# M7.net
KiCad netlist of a schematic drawn in Altium Designer
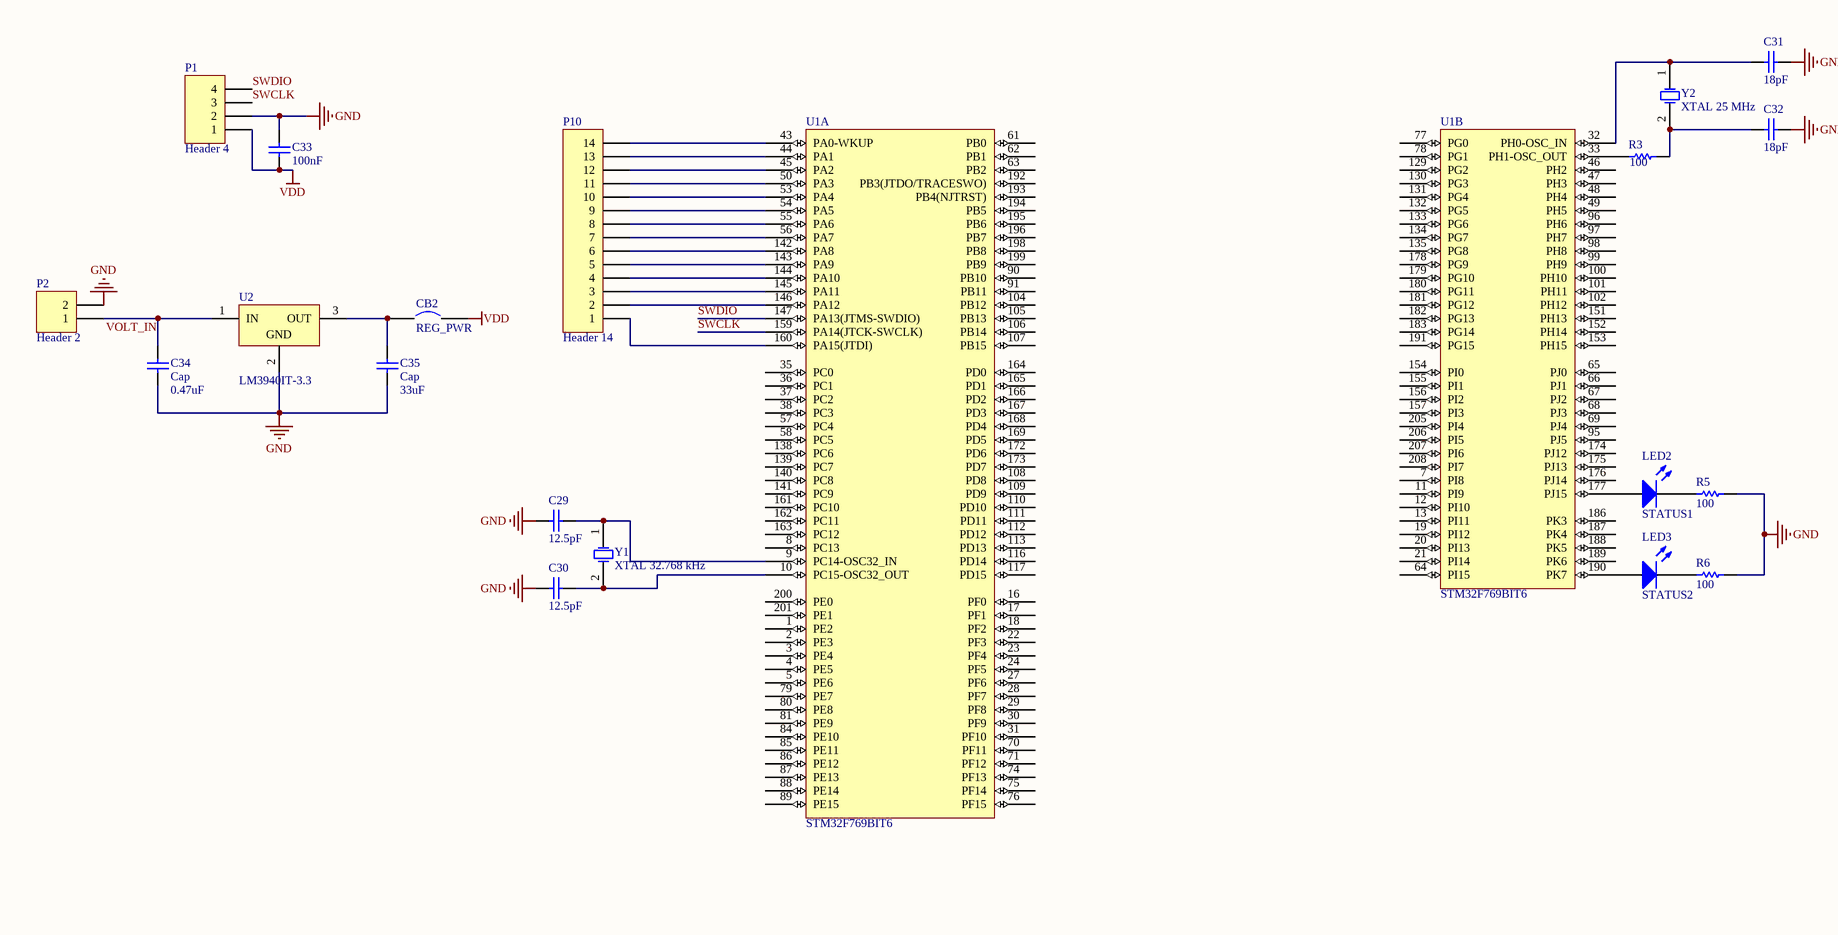
[diagram p0: M7.SchDoc, left]
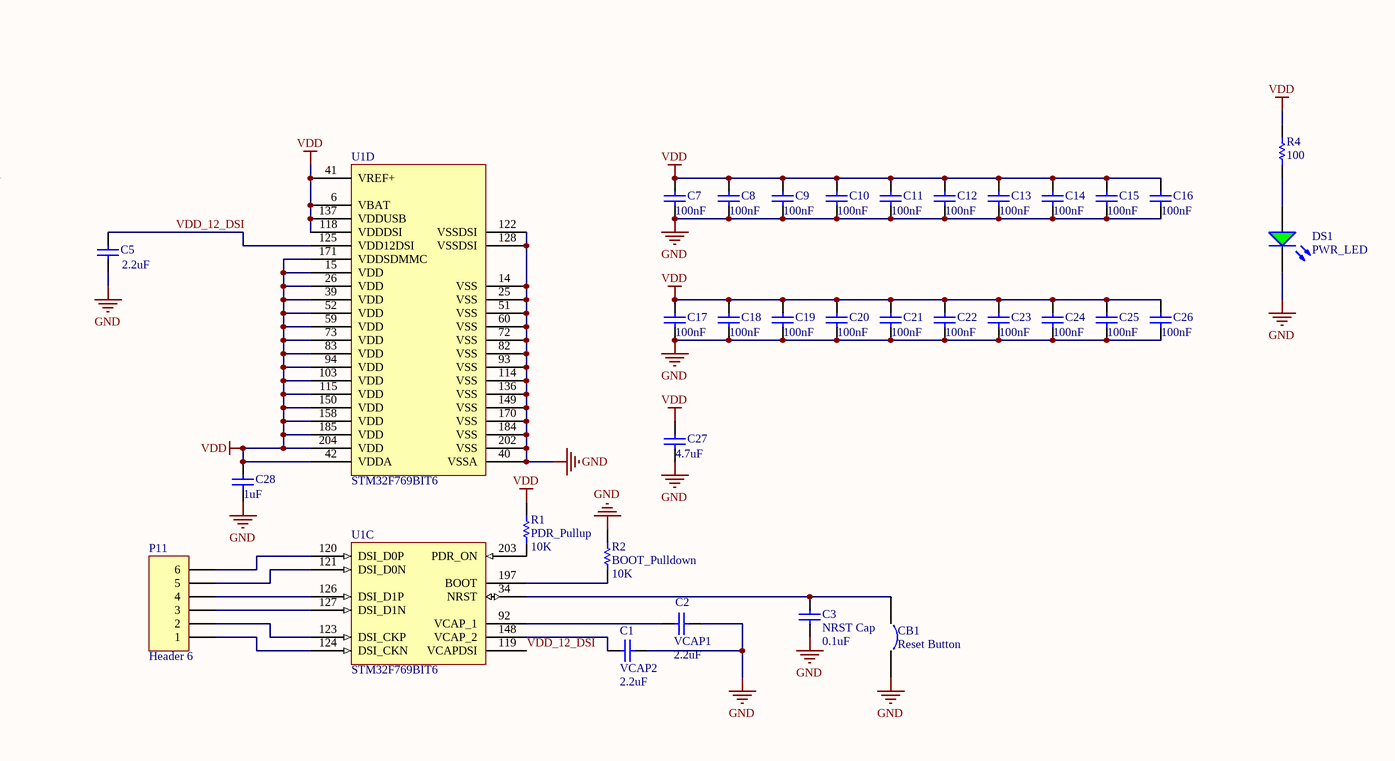
[diagram p1: M7.SchDoc, right]

(export (version "E")
  (design (tool "Eeschema 10.0.6"))
  (components
    (comp (ref "C1")
      (value "VCAP2")
      (footprint "C1206")
      (description "Capacitor (Semiconductor SIM Model)")
      (fields (field (name "ALTIUM_VALUE") "2.2uF") (field (name "PUBLISHER") "Altium Limited"))
      (libsource (lib "Miscellaneous Devices") (part "Cap Semi"))
    )
    (comp (ref "C2")
      (value "VCAP1")
      (footprint "C1206")
      (description "Capacitor (Semiconductor SIM Model)")
      (fields (field (name "ALTIUM_VALUE") "2.2uF") (field (name "PUBLISHER") "Altium Limited"))
      (libsource (lib "Miscellaneous Devices") (part "Cap Semi"))
    )
    (comp (ref "C3")
      (value "NRST Cap")
      (footprint "C1206")
      (description "Capacitor (Semiconductor SIM Model)")
      (fields (field (name "ALTIUM_VALUE") "0.1uF") (field (name "PUBLISHER") "Altium Limited"))
      (libsource (lib "Miscellaneous Devices") (part "Cap Semi"))
    )
    (comp (ref "C5")
      (value "2.2uF")
      (footprint "C1206")
      (description "Capacitor (Semiconductor SIM Model)")
      (fields (field (name "Comment") "DSI_Filter2") (field (name "PUBLISHER") "Altium Limited"))
      (libsource (lib "Miscellaneous Devices") (part "Cap Semi"))
    )
    (comp (ref "C7")
      (value "100nF")
      (footprint "C1206")
      (description "Capacitor (Semiconductor SIM Model)")
      (fields (field (name "Comment") "DSI_Filter3") (field (name "PUBLISHER") "Altium Limited"))
      (libsource (lib "Miscellaneous Devices") (part "Cap Semi"))
    )
    (comp (ref "C8")
      (value "100nF")
      (footprint "C1206")
      (description "Capacitor (Semiconductor SIM Model)")
      (fields (field (name "Comment") "DSI_Filter3") (field (name "PUBLISHER") "Altium Limited"))
      (libsource (lib "Miscellaneous Devices") (part "Cap Semi"))
    )
    (comp (ref "C9")
      (value "100nF")
      (footprint "C1206")
      (description "Capacitor (Semiconductor SIM Model)")
      (fields (field (name "Comment") "DSI_Filter3") (field (name "PUBLISHER") "Altium Limited"))
      (libsource (lib "Miscellaneous Devices") (part "Cap Semi"))
    )
    (comp (ref "C10")
      (value "100nF")
      (footprint "C1206")
      (description "Capacitor (Semiconductor SIM Model)")
      (fields (field (name "Comment") "DSI_Filter3") (field (name "PUBLISHER") "Altium Limited"))
      (libsource (lib "Miscellaneous Devices") (part "Cap Semi"))
    )
    (comp (ref "C11")
      (value "100nF")
      (footprint "C1206")
      (description "Capacitor (Semiconductor SIM Model)")
      (fields (field (name "Comment") "DSI_Filter3") (field (name "PUBLISHER") "Altium Limited"))
      (libsource (lib "Miscellaneous Devices") (part "Cap Semi"))
    )
    (comp (ref "C12")
      (value "100nF")
      (footprint "C1206")
      (description "Capacitor (Semiconductor SIM Model)")
      (fields (field (name "Comment") "DSI_Filter3") (field (name "PUBLISHER") "Altium Limited"))
      (libsource (lib "Miscellaneous Devices") (part "Cap Semi"))
    )
    (comp (ref "C13")
      (value "100nF")
      (footprint "C1206")
      (description "Capacitor (Semiconductor SIM Model)")
      (fields (field (name "Comment") "DSI_Filter3") (field (name "PUBLISHER") "Altium Limited"))
      (libsource (lib "Miscellaneous Devices") (part "Cap Semi"))
    )
    (comp (ref "C14")
      (value "100nF")
      (footprint "C1206")
      (description "Capacitor (Semiconductor SIM Model)")
      (fields (field (name "Comment") "DSI_Filter3") (field (name "PUBLISHER") "Altium Limited"))
      (libsource (lib "Miscellaneous Devices") (part "Cap Semi"))
    )
    (comp (ref "C15")
      (value "100nF")
      (footprint "C1206")
      (description "Capacitor (Semiconductor SIM Model)")
      (fields (field (name "Comment") "DSI_Filter3") (field (name "PUBLISHER") "Altium Limited"))
      (libsource (lib "Miscellaneous Devices") (part "Cap Semi"))
    )
    (comp (ref "C16")
      (value "100nF")
      (footprint "C1206")
      (description "Capacitor (Semiconductor SIM Model)")
      (fields (field (name "Comment") "DSI_Filter3") (field (name "PUBLISHER") "Altium Limited"))
      (libsource (lib "Miscellaneous Devices") (part "Cap Semi"))
    )
    (comp (ref "C17")
      (value "100nF")
      (footprint "C1206")
      (description "Capacitor (Semiconductor SIM Model)")
      (fields (field (name "Comment") "DSI_Filter3") (field (name "PUBLISHER") "Altium Limited"))
      (libsource (lib "Miscellaneous Devices") (part "Cap Semi"))
    )
    (comp (ref "C18")
      (value "100nF")
      (footprint "C1206")
      (description "Capacitor (Semiconductor SIM Model)")
      (fields (field (name "Comment") "DSI_Filter3") (field (name "PUBLISHER") "Altium Limited"))
      (libsource (lib "Miscellaneous Devices") (part "Cap Semi"))
    )
    (comp (ref "C19")
      (value "100nF")
      (footprint "C1206")
      (description "Capacitor (Semiconductor SIM Model)")
      (fields (field (name "Comment") "DSI_Filter3") (field (name "PUBLISHER") "Altium Limited"))
      (libsource (lib "Miscellaneous Devices") (part "Cap Semi"))
    )
    (comp (ref "C20")
      (value "100nF")
      (footprint "C1206")
      (description "Capacitor (Semiconductor SIM Model)")
      (fields (field (name "Comment") "DSI_Filter3") (field (name "PUBLISHER") "Altium Limited"))
      (libsource (lib "Miscellaneous Devices") (part "Cap Semi"))
    )
    (comp (ref "C21")
      (value "100nF")
      (footprint "C1206")
      (description "Capacitor (Semiconductor SIM Model)")
      (fields (field (name "Comment") "DSI_Filter3") (field (name "PUBLISHER") "Altium Limited"))
      (libsource (lib "Miscellaneous Devices") (part "Cap Semi"))
    )
    (comp (ref "C22")
      (value "100nF")
      (footprint "C1206")
      (description "Capacitor (Semiconductor SIM Model)")
      (fields (field (name "Comment") "DSI_Filter3") (field (name "PUBLISHER") "Altium Limited"))
      (libsource (lib "Miscellaneous Devices") (part "Cap Semi"))
    )
    (comp (ref "C23")
      (value "100nF")
      (footprint "C1206")
      (description "Capacitor (Semiconductor SIM Model)")
      (fields (field (name "Comment") "DSI_Filter3") (field (name "PUBLISHER") "Altium Limited"))
      (libsource (lib "Miscellaneous Devices") (part "Cap Semi"))
    )
    (comp (ref "C24")
      (value "100nF")
      (footprint "C1206")
      (description "Capacitor (Semiconductor SIM Model)")
      (fields (field (name "Comment") "DSI_Filter3") (field (name "PUBLISHER") "Altium Limited"))
      (libsource (lib "Miscellaneous Devices") (part "Cap Semi"))
    )
    (comp (ref "C25")
      (value "100nF")
      (footprint "C1206")
      (description "Capacitor (Semiconductor SIM Model)")
      (fields (field (name "Comment") "DSI_Filter3") (field (name "PUBLISHER") "Altium Limited"))
      (libsource (lib "Miscellaneous Devices") (part "Cap Semi"))
    )
    (comp (ref "C26")
      (value "100nF")
      (footprint "C1206")
      (description "Capacitor (Semiconductor SIM Model)")
      (fields (field (name "Comment") "DSI_Filter3") (field (name "PUBLISHER") "Altium Limited"))
      (libsource (lib "Miscellaneous Devices") (part "Cap Semi"))
    )
    (comp (ref "C27")
      (value "4.7uF")
      (footprint "C1206")
      (description "Capacitor (Semiconductor SIM Model)")
      (fields (field (name "Comment") "DSI_Filter3") (field (name "PUBLISHER") "Altium Limited"))
      (libsource (lib "Miscellaneous Devices") (part "Cap Semi"))
    )
    (comp (ref "C28")
      (value "1uF")
      (footprint "C1206")
      (description "Capacitor (Semiconductor SIM Model)")
      (fields (field (name "Comment") "DSI_Filter3") (field (name "PUBLISHER") "Altium Limited"))
      (libsource (lib "Miscellaneous Devices") (part "Cap Semi"))
    )
    (comp (ref "C29")
      (value "12.5pF")
      (footprint "C1206")
      (description "Capacitor (Semiconductor SIM Model)")
      (fields (field (name "Comment") "DSI_Filter3") (field (name "PUBLISHER") "Altium Limited"))
      (libsource (lib "Miscellaneous Devices") (part "Cap Semi"))
    )
    (comp (ref "C30")
      (value "12.5pF")
      (footprint "C1206")
      (description "Capacitor (Semiconductor SIM Model)")
      (fields (field (name "Comment") "DSI_Filter3") (field (name "PUBLISHER") "Altium Limited"))
      (libsource (lib "Miscellaneous Devices") (part "Cap Semi"))
    )
    (comp (ref "C31")
      (value "18pF")
      (footprint "C1206")
      (description "Capacitor (Semiconductor SIM Model)")
      (fields (field (name "Comment") "DSI_Filter3") (field (name "PUBLISHER") "Altium Limited"))
      (libsource (lib "Miscellaneous Devices") (part "Cap Semi"))
    )
    (comp (ref "C32")
      (value "18pF")
      (footprint "C1206")
      (description "Capacitor (Semiconductor SIM Model)")
      (fields (field (name "Comment") "DSI_Filter3") (field (name "PUBLISHER") "Altium Limited"))
      (libsource (lib "Miscellaneous Devices") (part "Cap Semi"))
    )
    (comp (ref "C33")
      (value "100nF")
      (footprint "C1206")
      (description "Capacitor (Semiconductor SIM Model)")
      (fields (field (name "Comment") "DSI_Filter3") (field (name "PUBLISHER") "Altium Limited"))
      (libsource (lib "Miscellaneous Devices") (part "Cap Semi"))
    )
    (comp (ref "C34")
      (value "Cap")
      (footprint "RAD-0.3")
      (description "Capacitor")
      (fields (field (name "ALTIUM_VALUE") "0.47uF") (field (name "PUBLISHER") "Altium Limited"))
      (libsource (lib "Miscellaneous Devices") (part "Cap"))
    )
    (comp (ref "C35")
      (value "Cap")
      (footprint "RAD-0.3")
      (description "Capacitor")
      (fields (field (name "ALTIUM_VALUE") "33uF") (field (name "PUBLISHER") "Altium Limited"))
      (libsource (lib "Miscellaneous Devices") (part "Cap"))
    )
    (comp (ref "CB1")
      (value "Reset Button")
      (footprint "SPST-2")
      (description "Circuit Breaker")
      (fields (field (name "PUBLISHER") "Altium Limited"))
      (libsource (lib "Miscellaneous Devices") (part "Circuit Breaker"))
    )
    (comp (ref "CB2")
      (value "REG_PWR")
      (footprint "SPST-2")
      (description "Circuit Breaker")
      (fields (field (name "PUBLISHER") "Altium Limited"))
      (libsource (lib "Miscellaneous Devices") (part "Circuit Breaker"))
    )
    (comp (ref "DS1")
      (value "PWR_LED")
      (footprint "AVAG-HLMP-4740")
      (description "T-1 3/4 (5 mm) Low Current LED Lamp, Green, 1.9 V, -20 to 100 degC, 2-Pin THD, RoHS, Bulk")
      (fields (field (name "MANUFACTURER") "AvagoTechnologies"))
      (libsource (lib "Altium Content Vault") (part "LED-GREEN-AK-2"))
    )
    (comp (ref "LED2")
      (value "STATUS1")
      (footprint "Type 5mm")
      (description "THT LED round mono-color waterclear, WL-TMRW ,Blue")
      (fields (field (name "MANUFACTURER") "Wuerth Elektronik") (field (name "PARTNUMBER") "151053BS04500"))
      (libsource (lib "Altium Content Vault") (part "WE-LED_K1A2-2"))
    )
    (comp (ref "LED3")
      (value "STATUS2")
      (footprint "Type 5mm")
      (description "THT LED round mono-color waterclear, WL-TMRW ,Blue")
      (fields (field (name "MANUFACTURER") "Wuerth Elektronik") (field (name "PARTNUMBER") "151053BS04500"))
      (libsource (lib "Altium Content Vault") (part "WE-LED_K1A2-2"))
    )
    (comp (ref "P1")
      (value "Header 4")
      (footprint "HDR1X4")
      (description "Header, 4-Pin")
      (fields (field (name "PUBLISHER") "Altium Limited"))
      (libsource (lib "Miscellaneous Connectors") (part "Header 4"))
    )
    (comp (ref "P2")
      (value "Header 2")
      (footprint "HDR1X2")
      (description "Header, 2-Pin")
      (fields (field (name "PUBLISHER") "Altium Limited"))
      (libsource (lib "Miscellaneous Connectors") (part "Header 2"))
    )
    (comp (ref "P10")
      (value "Header 14")
      (footprint "HDR1X14")
      (description "Header, 14-Pin")
      (fields (field (name "PUBLISHER") "Altium Limited"))
      (libsource (lib "Miscellaneous Connectors") (part "Header 14"))
    )
    (comp (ref "P11")
      (value "Header 6")
      (footprint "HDR1X6")
      (description "Header, 6-Pin")
      (fields (field (name "PUBLISHER") "Altium Limited"))
      (libsource (lib "Miscellaneous Connectors") (part "Header 6"))
    )
    (comp (ref "R1")
      (value "PDR_Pullup")
      (footprint "AXIAL-0.3")
      (description "Resistor")
      (fields (field (name "ALTIUM_VALUE") "10K") (field (name "PUBLISHER") "Altium Limited"))
      (libsource (lib "Miscellaneous Devices") (part "Res1"))
    )
    (comp (ref "R2")
      (value "BOOT_Pulldown")
      (footprint "AXIAL-0.3")
      (description "Resistor")
      (fields (field (name "ALTIUM_VALUE") "10K") (field (name "PUBLISHER") "Altium Limited"))
      (libsource (lib "Miscellaneous Devices") (part "Res1"))
    )
    (comp (ref "R3")
      (value "100")
      (footprint "AXIAL-0.3")
      (description "Resistor")
      (fields (field (name "Comment") "Inverter_Lim") (field (name "PUBLISHER") "Altium Limited"))
      (libsource (lib "Miscellaneous Devices") (part "Res1"))
    )
    (comp (ref "R4")
      (value "100")
      (footprint "AXIAL-0.3")
      (description "Resistor")
      (fields (field (name "Comment") "Inverter_Lim") (field (name "PUBLISHER") "Altium Limited"))
      (libsource (lib "Miscellaneous Devices") (part "Res1"))
    )
    (comp (ref "R5")
      (value "100")
      (footprint "AXIAL-0.3")
      (description "Resistor")
      (fields (field (name "Comment") "Inverter_Lim") (field (name "PUBLISHER") "Altium Limited"))
      (libsource (lib "Miscellaneous Devices") (part "Res1"))
    )
    (comp (ref "R6")
      (value "100")
      (footprint "AXIAL-0.3")
      (description "Resistor")
      (fields (field (name "Comment") "Inverter_Lim") (field (name "PUBLISHER") "Altium Limited"))
      (libsource (lib "Miscellaneous Devices") (part "Res1"))
    )
    (comp (ref "U1")
      (value "STM32F769BIT6")
      (footprint "STM-LQFP208_V")
      (fields (field (name "MANUFACTURER") "STMicroelectronics"))
      (libsource (lib "Altium Content Vault") (part "STM-STM32F769BIT6-LQFP-208"))
    )
    (comp (ref "U2")
      (value "LM3940IT-3.3")
      (footprint "NDE0003A")
      (description "1A Low Dropout Regulator for 5V to 3.3V Conversion, 3-pin TO-220")
      (fields (field (name "MANUFACTURER") "Texas Instruments"))
      (libsource (lib "Altium Content Vault") (part "PM-REG-LM2940-SIL3"))
    )
    (comp (ref "Y1")
      (value "XTAL 32.768 kHz")
      (footprint "R38")
      (description "Crystal Oscillator")
      (fields (field (name "PUBLISHER") "Altium Limited"))
      (libsource (lib "Miscellaneous Devices") (part "XTAL"))
    )
    (comp (ref "Y2")
      (value "XTAL 25 MHz")
      (footprint "R38")
      (description "Crystal Oscillator")
      (fields (field (name "PUBLISHER") "Altium Limited"))
      (libsource (lib "Miscellaneous Devices") (part "XTAL"))
    )
  )
  (nets
    (net (code "1") (name "/SWCLK") (class "Default")
      (node (ref "P1") (pin "3") (pinfunction "3_3") (pintype "passive"))
      (node (ref "U1") (pin "159") (pinfunction "PA14(JTCK-SWCLK)_159") (pintype "bidirectional"))
    )
    (net (code "2") (name "/SWDIO") (class "Default")
      (node (ref "P1") (pin "4") (pinfunction "4_4") (pintype "passive"))
      (node (ref "U1") (pin "147") (pinfunction "PA13(JTMS-SWDIO)_147") (pintype "bidirectional"))
    )
    (net (code "3") (name "/VDD_12_DSI") (class "Default")
      (node (ref "C5") (pin "2") (pinfunction "2_2") (pintype "passive"))
      (node (ref "U1") (pin "119") (pinfunction "VCAPDSI_119") (pintype "power_in"))
      (node (ref "U1") (pin "125") (pinfunction "VDD12DSI_125") (pintype "power_in"))
    )
    (net (code "4") (name "/VOLT_IN") (class "Default")
      (node (ref "C34") (pin "2") (pinfunction "2_2") (pintype "passive"))
      (node (ref "P2") (pin "1") (pinfunction "1_1") (pintype "passive"))
      (node (ref "U2") (pin "1") (pinfunction "IN_1") (pintype "power_in"))
    )
    (net (code "5") (name "GND") (class "Default")
      (node (ref "C1") (pin "2") (pinfunction "2_2") (pintype "passive"))
      (node (ref "C10") (pin "1") (pinfunction "1_1") (pintype "passive"))
      (node (ref "C11") (pin "1") (pinfunction "1_1") (pintype "passive"))
      (node (ref "C12") (pin "1") (pinfunction "1_1") (pintype "passive"))
      (node (ref "C13") (pin "1") (pinfunction "1_1") (pintype "passive"))
      (node (ref "C14") (pin "1") (pinfunction "1_1") (pintype "passive"))
      (node (ref "C15") (pin "1") (pinfunction "1_1") (pintype "passive"))
      (node (ref "C16") (pin "1") (pinfunction "1_1") (pintype "passive"))
      (node (ref "C17") (pin "1") (pinfunction "1_1") (pintype "passive"))
      (node (ref "C18") (pin "1") (pinfunction "1_1") (pintype "passive"))
      (node (ref "C19") (pin "1") (pinfunction "1_1") (pintype "passive"))
      (node (ref "C2") (pin "2") (pinfunction "2_2") (pintype "passive"))
      (node (ref "C20") (pin "1") (pinfunction "1_1") (pintype "passive"))
      (node (ref "C21") (pin "1") (pinfunction "1_1") (pintype "passive"))
      (node (ref "C22") (pin "1") (pinfunction "1_1") (pintype "passive"))
      (node (ref "C23") (pin "1") (pinfunction "1_1") (pintype "passive"))
      (node (ref "C24") (pin "1") (pinfunction "1_1") (pintype "passive"))
      (node (ref "C25") (pin "1") (pinfunction "1_1") (pintype "passive"))
      (node (ref "C26") (pin "1") (pinfunction "1_1") (pintype "passive"))
      (node (ref "C27") (pin "1") (pinfunction "1_1") (pintype "passive"))
      (node (ref "C28") (pin "1") (pinfunction "1_1") (pintype "passive"))
      (node (ref "C29") (pin "2") (pinfunction "2_2") (pintype "passive"))
      (node (ref "C3") (pin "1") (pinfunction "1_1") (pintype "passive"))
      (node (ref "C30") (pin "2") (pinfunction "2_2") (pintype "passive"))
      (node (ref "C31") (pin "1") (pinfunction "1_1") (pintype "passive"))
      (node (ref "C32") (pin "1") (pinfunction "1_1") (pintype "passive"))
      (node (ref "C33") (pin "1") (pinfunction "1_1") (pintype "passive"))
      (node (ref "C34") (pin "1") (pinfunction "1_1") (pintype "passive"))
      (node (ref "C35") (pin "1") (pinfunction "1_1") (pintype "passive"))
      (node (ref "C5") (pin "1") (pinfunction "1_1") (pintype "passive"))
      (node (ref "C7") (pin "1") (pinfunction "1_1") (pintype "passive"))
      (node (ref "C8") (pin "1") (pinfunction "1_1") (pintype "passive"))
      (node (ref "C9") (pin "1") (pinfunction "1_1") (pintype "passive"))
      (node (ref "CB1") (pin "2") (pinfunction "2_2") (pintype "passive"))
      (node (ref "DS1") (pin "2") (pinfunction "K_2") (pintype "passive"))
      (node (ref "P1") (pin "2") (pinfunction "2_2") (pintype "passive"))
      (node (ref "P2") (pin "2") (pinfunction "2_2") (pintype "passive"))
      (node (ref "R2") (pin "1") (pinfunction "1_1") (pintype "passive"))
      (node (ref "R5") (pin "2") (pinfunction "2_2") (pintype "passive"))
      (node (ref "R6") (pin "2") (pinfunction "2_2") (pintype "passive"))
      (node (ref "U1") (pin "114") (pinfunction "VSS_114") (pintype "power_in"))
      (node (ref "U1") (pin "122") (pinfunction "VSSDSI_122") (pintype "power_in"))
      (node (ref "U1") (pin "128") (pinfunction "VSSDSI_128") (pintype "power_in"))
      (node (ref "U1") (pin "136") (pinfunction "VSS_136") (pintype "power_in"))
      (node (ref "U1") (pin "14") (pinfunction "VSS_14") (pintype "power_in"))
      (node (ref "U1") (pin "149") (pinfunction "VSS_149") (pintype "power_in"))
      (node (ref "U1") (pin "170") (pinfunction "VSS_170") (pintype "power_in"))
      (node (ref "U1") (pin "184") (pinfunction "VSS_184") (pintype "power_in"))
      (node (ref "U1") (pin "202") (pinfunction "VSS_202") (pintype "power_in"))
      (node (ref "U1") (pin "25") (pinfunction "VSS_25") (pintype "power_in"))
      (node (ref "U1") (pin "40") (pinfunction "VSSA_40") (pintype "power_in"))
      (node (ref "U1") (pin "51") (pinfunction "VSS_51") (pintype "power_in"))
      (node (ref "U1") (pin "60") (pinfunction "VSS_60") (pintype "power_in"))
      (node (ref "U1") (pin "72") (pinfunction "VSS_72") (pintype "power_in"))
      (node (ref "U1") (pin "82") (pinfunction "VSS_82") (pintype "power_in"))
      (node (ref "U1") (pin "93") (pinfunction "VSS_93") (pintype "power_in"))
      (node (ref "U2") (pin "2") (pinfunction "GND_2") (pintype "power_in"))
    )
    (net (code "6") (name "Net-(DS1-A)") (class "Default")
      (node (ref "DS1") (pin "1") (pinfunction "A_1") (pintype "passive"))
      (node (ref "R4") (pin "2") (pinfunction "2_2") (pintype "passive"))
    )
    (net (code "7") (name "Net-(LED2-A)") (class "Default")
      (node (ref "LED2") (pin "2") (pinfunction "A_2") (pintype "passive"))
      (node (ref "U1") (pin "177") (pinfunction "PJ15_177") (pintype "bidirectional"))
    )
    (net (code "8") (name "Net-(LED2-K)") (class "Default")
      (node (ref "LED2") (pin "1") (pinfunction "K_1") (pintype "passive"))
      (node (ref "R5") (pin "1") (pinfunction "1_1") (pintype "passive"))
    )
    (net (code "9") (name "Net-(LED3-A)") (class "Default")
      (node (ref "LED3") (pin "2") (pinfunction "A_2") (pintype "passive"))
      (node (ref "U1") (pin "190") (pinfunction "PK7_190") (pintype "bidirectional"))
    )
    (net (code "10") (name "Net-(LED3-K)") (class "Default")
      (node (ref "LED3") (pin "1") (pinfunction "K_1") (pintype "passive"))
      (node (ref "R6") (pin "1") (pinfunction "1_1") (pintype "passive"))
    )
    (net (code "11") (name "Net-(U1A-PA0-WKUP)") (class "Default")
      (node (ref "P10") (pin "14") (pinfunction "14_14") (pintype "passive"))
      (node (ref "U1") (pin "43") (pinfunction "PA0-WKUP_43") (pintype "bidirectional"))
    )
    (net (code "12") (name "Net-(U1A-PA1)") (class "Default")
      (node (ref "P10") (pin "13") (pinfunction "13_13") (pintype "passive"))
      (node (ref "U1") (pin "44") (pinfunction "PA1_44") (pintype "bidirectional"))
    )
    (net (code "13") (name "Net-(U1A-PA2)") (class "Default")
      (node (ref "P10") (pin "12") (pinfunction "12_12") (pintype "passive"))
      (node (ref "U1") (pin "45") (pinfunction "PA2_45") (pintype "bidirectional"))
    )
    (net (code "14") (name "Net-(U1A-PA3)") (class "Default")
      (node (ref "P10") (pin "11") (pinfunction "11_11") (pintype "passive"))
      (node (ref "U1") (pin "50") (pinfunction "PA3_50") (pintype "bidirectional"))
    )
    (net (code "15") (name "Net-(U1A-PA4)") (class "Default")
      (node (ref "P10") (pin "10") (pinfunction "10_10") (pintype "passive"))
      (node (ref "U1") (pin "53") (pinfunction "PA4_53") (pintype "bidirectional"))
    )
    (net (code "16") (name "Net-(U1A-PA5)") (class "Default")
      (node (ref "P10") (pin "9") (pinfunction "9_9") (pintype "passive"))
      (node (ref "U1") (pin "54") (pinfunction "PA5_54") (pintype "bidirectional"))
    )
    (net (code "17") (name "Net-(U1A-PA6)") (class "Default")
      (node (ref "P10") (pin "8") (pinfunction "8_8") (pintype "passive"))
      (node (ref "U1") (pin "55") (pinfunction "PA6_55") (pintype "bidirectional"))
    )
    (net (code "18") (name "Net-(U1A-PA7)") (class "Default")
      (node (ref "P10") (pin "7") (pinfunction "7_7") (pintype "passive"))
      (node (ref "U1") (pin "56") (pinfunction "PA7_56") (pintype "bidirectional"))
    )
    (net (code "19") (name "Net-(U1A-PA8)") (class "Default")
      (node (ref "P10") (pin "6") (pinfunction "6_6") (pintype "passive"))
      (node (ref "U1") (pin "142") (pinfunction "PA8_142") (pintype "bidirectional"))
    )
    (net (code "20") (name "Net-(U1A-PA9)") (class "Default")
      (node (ref "P10") (pin "5") (pinfunction "5_5") (pintype "passive"))
      (node (ref "U1") (pin "143") (pinfunction "PA9_143") (pintype "bidirectional"))
    )
    (net (code "21") (name "Net-(U1A-PA10)") (class "Default")
      (node (ref "P10") (pin "4") (pinfunction "4_4") (pintype "passive"))
      (node (ref "U1") (pin "144") (pinfunction "PA10_144") (pintype "bidirectional"))
    )
    (net (code "22") (name "Net-(U1A-PA11)") (class "Default")
      (node (ref "P10") (pin "3") (pinfunction "3_3") (pintype "passive"))
      (node (ref "U1") (pin "145") (pinfunction "PA11_145") (pintype "bidirectional"))
    )
    (net (code "23") (name "Net-(U1A-PA12)") (class "Default")
      (node (ref "P10") (pin "2") (pinfunction "2_2") (pintype "passive"))
      (node (ref "U1") (pin "146") (pinfunction "PA12_146") (pintype "bidirectional"))
    )
    (net (code "24") (name "Net-(U1A-PA15(JTDI))") (class "Default")
      (node (ref "P10") (pin "1") (pinfunction "1_1") (pintype "passive"))
      (node (ref "U1") (pin "160") (pinfunction "PA15(JTDI)_160") (pintype "bidirectional"))
    )
    (net (code "25") (name "Net-(U1A-PC14-OSC32_IN)") (class "Default")
      (node (ref "C29") (pin "1") (pinfunction "1_1") (pintype "passive"))
      (node (ref "U1") (pin "9") (pinfunction "PC14-OSC32_IN_9") (pintype "bidirectional"))
      (node (ref "Y1") (pin "1") (pinfunction "OSC1_1") (pintype "passive"))
    )
    (net (code "26") (name "Net-(U1A-PC15-OSC32_OUT)") (class "Default")
      (node (ref "C30") (pin "1") (pinfunction "1_1") (pintype "passive"))
      (node (ref "U1") (pin "10") (pinfunction "PC15-OSC32_OUT_10") (pintype "bidirectional"))
      (node (ref "Y1") (pin "2") (pinfunction "OSC2_2") (pintype "passive"))
    )
    (net (code "27") (name "Net-(U1B-PH0-OSC_IN)") (class "Default")
      (node (ref "C31") (pin "2") (pinfunction "2_2") (pintype "passive"))
      (node (ref "U1") (pin "32") (pinfunction "PH0-OSC_IN_32") (pintype "bidirectional"))
      (node (ref "Y2") (pin "1") (pinfunction "OSC1_1") (pintype "passive"))
    )
    (net (code "28") (name "Net-(U1B-PH1-OSC_OUT)") (class "Default")
      (node (ref "R3") (pin "2") (pinfunction "2_2") (pintype "passive"))
      (node (ref "U1") (pin "33") (pinfunction "PH1-OSC_OUT_33") (pintype "bidirectional"))
    )
    (net (code "29") (name "Net-(U1C-BOOT)") (class "Default")
      (node (ref "R2") (pin "2") (pinfunction "2_2") (pintype "passive"))
      (node (ref "U1") (pin "197") (pinfunction "BOOT_197") (pintype "power_in"))
    )
    (net (code "30") (name "Net-(U1C-DSI_CKN)") (class "Default")
      (node (ref "P11") (pin "1") (pinfunction "1_1") (pintype "passive"))
      (node (ref "U1") (pin "124") (pinfunction "DSI_CKN_124") (pintype "input"))
    )
    (net (code "31") (name "Net-(U1C-DSI_CKP)") (class "Default")
      (node (ref "P11") (pin "2") (pinfunction "2_2") (pintype "passive"))
      (node (ref "U1") (pin "123") (pinfunction "DSI_CKP_123") (pintype "input"))
    )
    (net (code "32") (name "Net-(U1C-DSI_D0N)") (class "Default")
      (node (ref "P11") (pin "5") (pinfunction "5_5") (pintype "passive"))
      (node (ref "U1") (pin "121") (pinfunction "DSI_D0N_121") (pintype "input"))
    )
    (net (code "33") (name "Net-(U1C-DSI_D0P)") (class "Default")
      (node (ref "P11") (pin "6") (pinfunction "6_6") (pintype "passive"))
      (node (ref "U1") (pin "120") (pinfunction "DSI_D0P_120") (pintype "input"))
    )
    (net (code "34") (name "Net-(U1C-DSI_D1N)") (class "Default")
      (node (ref "P11") (pin "3") (pinfunction "3_3") (pintype "passive"))
      (node (ref "U1") (pin "127") (pinfunction "DSI_D1N_127") (pintype "input"))
    )
    (net (code "35") (name "Net-(U1C-DSI_D1P)") (class "Default")
      (node (ref "P11") (pin "4") (pinfunction "4_4") (pintype "passive"))
      (node (ref "U1") (pin "126") (pinfunction "DSI_D1P_126") (pintype "input"))
    )
    (net (code "36") (name "Net-(U1C-NRST)") (class "Default")
      (node (ref "C3") (pin "2") (pinfunction "2_2") (pintype "passive"))
      (node (ref "CB1") (pin "1") (pinfunction "1_1") (pintype "passive"))
      (node (ref "U1") (pin "34") (pinfunction "NRST_34") (pintype "bidirectional"))
    )
    (net (code "37") (name "Net-(U1C-PDR_ON)") (class "Default")
      (node (ref "R1") (pin "1") (pinfunction "1_1") (pintype "passive"))
      (node (ref "U1") (pin "203") (pinfunction "PDR_ON_203") (pintype "input"))
    )
    (net (code "38") (name "Net-(U1C-VCAP_1)") (class "Default")
      (node (ref "C2") (pin "1") (pinfunction "1_1") (pintype "passive"))
      (node (ref "U1") (pin "92") (pinfunction "VCAP_1_92") (pintype "power_in"))
    )
    (net (code "39") (name "Net-(U1C-VCAP_2)") (class "Default")
      (node (ref "C1") (pin "1") (pinfunction "1_1") (pintype "passive"))
      (node (ref "U1") (pin "148") (pinfunction "VCAP_2_148") (pintype "power_in"))
    )
    (net (code "40") (name "Net-(U2-OUT)") (class "Default")
      (node (ref "C35") (pin "2") (pinfunction "2_2") (pintype "passive"))
      (node (ref "CB2") (pin "1") (pinfunction "1_1") (pintype "passive"))
      (node (ref "U2") (pin "3") (pinfunction "OUT_3") (pintype "power_in"))
    )
    (net (code "41") (name "Net-(Y2-OSC2)") (class "Default")
      (node (ref "C32") (pin "2") (pinfunction "2_2") (pintype "passive"))
      (node (ref "R3") (pin "1") (pinfunction "1_1") (pintype "passive"))
      (node (ref "Y2") (pin "2") (pinfunction "OSC2_2") (pintype "passive"))
    )
    (net (code "42") (name "VDD") (class "Default")
      (node (ref "C10") (pin "2") (pinfunction "2_2") (pintype "passive"))
      (node (ref "C11") (pin "2") (pinfunction "2_2") (pintype "passive"))
      (node (ref "C12") (pin "2") (pinfunction "2_2") (pintype "passive"))
      (node (ref "C13") (pin "2") (pinfunction "2_2") (pintype "passive"))
      (node (ref "C14") (pin "2") (pinfunction "2_2") (pintype "passive"))
      (node (ref "C15") (pin "2") (pinfunction "2_2") (pintype "passive"))
      (node (ref "C16") (pin "2") (pinfunction "2_2") (pintype "passive"))
      (node (ref "C17") (pin "2") (pinfunction "2_2") (pintype "passive"))
      (node (ref "C18") (pin "2") (pinfunction "2_2") (pintype "passive"))
      (node (ref "C19") (pin "2") (pinfunction "2_2") (pintype "passive"))
      (node (ref "C20") (pin "2") (pinfunction "2_2") (pintype "passive"))
      (node (ref "C21") (pin "2") (pinfunction "2_2") (pintype "passive"))
      (node (ref "C22") (pin "2") (pinfunction "2_2") (pintype "passive"))
      (node (ref "C23") (pin "2") (pinfunction "2_2") (pintype "passive"))
      (node (ref "C24") (pin "2") (pinfunction "2_2") (pintype "passive"))
      (node (ref "C25") (pin "2") (pinfunction "2_2") (pintype "passive"))
      (node (ref "C26") (pin "2") (pinfunction "2_2") (pintype "passive"))
      (node (ref "C27") (pin "2") (pinfunction "2_2") (pintype "passive"))
      (node (ref "C28") (pin "2") (pinfunction "2_2") (pintype "passive"))
      (node (ref "C33") (pin "2") (pinfunction "2_2") (pintype "passive"))
      (node (ref "C7") (pin "2") (pinfunction "2_2") (pintype "passive"))
      (node (ref "C8") (pin "2") (pinfunction "2_2") (pintype "passive"))
      (node (ref "C9") (pin "2") (pinfunction "2_2") (pintype "passive"))
      (node (ref "CB2") (pin "2") (pinfunction "2_2") (pintype "passive"))
      (node (ref "P1") (pin "1") (pinfunction "1_1") (pintype "passive"))
      (node (ref "R1") (pin "2") (pinfunction "2_2") (pintype "passive"))
      (node (ref "R4") (pin "1") (pinfunction "1_1") (pintype "passive"))
      (node (ref "U1") (pin "103") (pinfunction "VDD_103") (pintype "power_in"))
      (node (ref "U1") (pin "115") (pinfunction "VDD_115") (pintype "power_in"))
      (node (ref "U1") (pin "118") (pinfunction "VDDDSI_118") (pintype "power_in"))
      (node (ref "U1") (pin "137") (pinfunction "VDDUSB_137") (pintype "power_in"))
      (node (ref "U1") (pin "15") (pinfunction "VDD_15") (pintype "power_in"))
      (node (ref "U1") (pin "150") (pinfunction "VDD_150") (pintype "power_in"))
      (node (ref "U1") (pin "158") (pinfunction "VDD_158") (pintype "power_in"))
      (node (ref "U1") (pin "171") (pinfunction "VDDSDMMC_171") (pintype "power_in"))
      (node (ref "U1") (pin "185") (pinfunction "VDD_185") (pintype "power_in"))
      (node (ref "U1") (pin "204") (pinfunction "VDD_204") (pintype "power_in"))
      (node (ref "U1") (pin "26") (pinfunction "VDD_26") (pintype "power_in"))
      (node (ref "U1") (pin "39") (pinfunction "VDD_39") (pintype "power_in"))
      (node (ref "U1") (pin "41") (pinfunction "VREF+_41") (pintype "power_in"))
      (node (ref "U1") (pin "42") (pinfunction "VDDA_42") (pintype "power_in"))
      (node (ref "U1") (pin "52") (pinfunction "VDD_52") (pintype "power_in"))
      (node (ref "U1") (pin "59") (pinfunction "VDD_59") (pintype "power_in"))
      (node (ref "U1") (pin "6") (pinfunction "VBAT_6") (pintype "power_in"))
      (node (ref "U1") (pin "73") (pinfunction "VDD_73") (pintype "power_in"))
      (node (ref "U1") (pin "83") (pinfunction "VDD_83") (pintype "power_in"))
      (node (ref "U1") (pin "94") (pinfunction "VDD_94") (pintype "power_in"))
    )
    (net (code "43") (name "unconnected-(U1A-PB0-Pad61)") (class "Default")
      (node (ref "U1") (pin "61") (pinfunction "PB0_61") (pintype "bidirectional"))
    )
    (net (code "44") (name "unconnected-(U1A-PB1-Pad62)") (class "Default")
      (node (ref "U1") (pin "62") (pinfunction "PB1_62") (pintype "bidirectional"))
    )
    (net (code "45") (name "unconnected-(U1A-PB2-Pad63)") (class "Default")
      (node (ref "U1") (pin "63") (pinfunction "PB2_63") (pintype "bidirectional"))
    )
    (net (code "46") (name "unconnected-(U1A-PB3(JTDO{slash}TRACESWO)-Pad192)") (class "Default")
      (node (ref "U1") (pin "192") (pinfunction "PB3(JTDO/TRACESWO)_192") (pintype "bidirectional"))
    )
    (net (code "47") (name "unconnected-(U1A-PB4(NJTRST)-Pad193)") (class "Default")
      (node (ref "U1") (pin "193") (pinfunction "PB4(NJTRST)_193") (pintype "bidirectional"))
    )
    (net (code "48") (name "unconnected-(U1A-PB5-Pad194)") (class "Default")
      (node (ref "U1") (pin "194") (pinfunction "PB5_194") (pintype "bidirectional"))
    )
    (net (code "49") (name "unconnected-(U1A-PB6-Pad195)") (class "Default")
      (node (ref "U1") (pin "195") (pinfunction "PB6_195") (pintype "bidirectional"))
    )
    (net (code "50") (name "unconnected-(U1A-PB7-Pad196)") (class "Default")
      (node (ref "U1") (pin "196") (pinfunction "PB7_196") (pintype "bidirectional"))
    )
    (net (code "51") (name "unconnected-(U1A-PB8-Pad198)") (class "Default")
      (node (ref "U1") (pin "198") (pinfunction "PB8_198") (pintype "bidirectional"))
    )
    (net (code "52") (name "unconnected-(U1A-PB9-Pad199)") (class "Default")
      (node (ref "U1") (pin "199") (pinfunction "PB9_199") (pintype "bidirectional"))
    )
    (net (code "53") (name "unconnected-(U1A-PB10-Pad90)") (class "Default")
      (node (ref "U1") (pin "90") (pinfunction "PB10_90") (pintype "bidirectional"))
    )
    (net (code "54") (name "unconnected-(U1A-PB11-Pad91)") (class "Default")
      (node (ref "U1") (pin "91") (pinfunction "PB11_91") (pintype "bidirectional"))
    )
    (net (code "55") (name "unconnected-(U1A-PB12-Pad104)") (class "Default")
      (node (ref "U1") (pin "104") (pinfunction "PB12_104") (pintype "bidirectional"))
    )
    (net (code "56") (name "unconnected-(U1A-PB13-Pad105)") (class "Default")
      (node (ref "U1") (pin "105") (pinfunction "PB13_105") (pintype "bidirectional"))
    )
    (net (code "57") (name "unconnected-(U1A-PB14-Pad106)") (class "Default")
      (node (ref "U1") (pin "106") (pinfunction "PB14_106") (pintype "bidirectional"))
    )
    (net (code "58") (name "unconnected-(U1A-PB15-Pad107)") (class "Default")
      (node (ref "U1") (pin "107") (pinfunction "PB15_107") (pintype "bidirectional"))
    )
    (net (code "59") (name "unconnected-(U1A-PC0-Pad35)") (class "Default")
      (node (ref "U1") (pin "35") (pinfunction "PC0_35") (pintype "bidirectional"))
    )
    (net (code "60") (name "unconnected-(U1A-PC1-Pad36)") (class "Default")
      (node (ref "U1") (pin "36") (pinfunction "PC1_36") (pintype "bidirectional"))
    )
    (net (code "61") (name "unconnected-(U1A-PC2-Pad37)") (class "Default")
      (node (ref "U1") (pin "37") (pinfunction "PC2_37") (pintype "bidirectional"))
    )
    (net (code "62") (name "unconnected-(U1A-PC3-Pad38)") (class "Default")
      (node (ref "U1") (pin "38") (pinfunction "PC3_38") (pintype "bidirectional"))
    )
    (net (code "63") (name "unconnected-(U1A-PC4-Pad57)") (class "Default")
      (node (ref "U1") (pin "57") (pinfunction "PC4_57") (pintype "bidirectional"))
    )
    (net (code "64") (name "unconnected-(U1A-PC5-Pad58)") (class "Default")
      (node (ref "U1") (pin "58") (pinfunction "PC5_58") (pintype "bidirectional"))
    )
    (net (code "65") (name "unconnected-(U1A-PC6-Pad138)") (class "Default")
      (node (ref "U1") (pin "138") (pinfunction "PC6_138") (pintype "bidirectional"))
    )
    (net (code "66") (name "unconnected-(U1A-PC7-Pad139)") (class "Default")
      (node (ref "U1") (pin "139") (pinfunction "PC7_139") (pintype "bidirectional"))
    )
    (net (code "67") (name "unconnected-(U1A-PC8-Pad140)") (class "Default")
      (node (ref "U1") (pin "140") (pinfunction "PC8_140") (pintype "bidirectional"))
    )
    (net (code "68") (name "unconnected-(U1A-PC9-Pad141)") (class "Default")
      (node (ref "U1") (pin "141") (pinfunction "PC9_141") (pintype "bidirectional"))
    )
    (net (code "69") (name "unconnected-(U1A-PC10-Pad161)") (class "Default")
      (node (ref "U1") (pin "161") (pinfunction "PC10_161") (pintype "bidirectional"))
    )
    (net (code "70") (name "unconnected-(U1A-PC11-Pad162)") (class "Default")
      (node (ref "U1") (pin "162") (pinfunction "PC11_162") (pintype "bidirectional"))
    )
    (net (code "71") (name "unconnected-(U1A-PC12-Pad163)") (class "Default")
      (node (ref "U1") (pin "163") (pinfunction "PC12_163") (pintype "bidirectional"))
    )
    (net (code "72") (name "unconnected-(U1A-PC13-Pad8)") (class "Default")
      (node (ref "U1") (pin "8") (pinfunction "PC13_8") (pintype "bidirectional"))
    )
    (net (code "73") (name "unconnected-(U1A-PD0-Pad164)") (class "Default")
      (node (ref "U1") (pin "164") (pinfunction "PD0_164") (pintype "bidirectional"))
    )
    (net (code "74") (name "unconnected-(U1A-PD1-Pad165)") (class "Default")
      (node (ref "U1") (pin "165") (pinfunction "PD1_165") (pintype "bidirectional"))
    )
    (net (code "75") (name "unconnected-(U1A-PD2-Pad166)") (class "Default")
      (node (ref "U1") (pin "166") (pinfunction "PD2_166") (pintype "bidirectional"))
    )
    (net (code "76") (name "unconnected-(U1A-PD3-Pad167)") (class "Default")
      (node (ref "U1") (pin "167") (pinfunction "PD3_167") (pintype "bidirectional"))
    )
    (net (code "77") (name "unconnected-(U1A-PD4-Pad168)") (class "Default")
      (node (ref "U1") (pin "168") (pinfunction "PD4_168") (pintype "bidirectional"))
    )
    (net (code "78") (name "unconnected-(U1A-PD5-Pad169)") (class "Default")
      (node (ref "U1") (pin "169") (pinfunction "PD5_169") (pintype "bidirectional"))
    )
    (net (code "79") (name "unconnected-(U1A-PD6-Pad172)") (class "Default")
      (node (ref "U1") (pin "172") (pinfunction "PD6_172") (pintype "bidirectional"))
    )
    (net (code "80") (name "unconnected-(U1A-PD7-Pad173)") (class "Default")
      (node (ref "U1") (pin "173") (pinfunction "PD7_173") (pintype "bidirectional"))
    )
    (net (code "81") (name "unconnected-(U1A-PD8-Pad108)") (class "Default")
      (node (ref "U1") (pin "108") (pinfunction "PD8_108") (pintype "bidirectional"))
    )
    (net (code "82") (name "unconnected-(U1A-PD9-Pad109)") (class "Default")
      (node (ref "U1") (pin "109") (pinfunction "PD9_109") (pintype "bidirectional"))
    )
    (net (code "83") (name "unconnected-(U1A-PD10-Pad110)") (class "Default")
      (node (ref "U1") (pin "110") (pinfunction "PD10_110") (pintype "bidirectional"))
    )
    (net (code "84") (name "unconnected-(U1A-PD11-Pad111)") (class "Default")
      (node (ref "U1") (pin "111") (pinfunction "PD11_111") (pintype "bidirectional"))
    )
    (net (code "85") (name "unconnected-(U1A-PD12-Pad112)") (class "Default")
      (node (ref "U1") (pin "112") (pinfunction "PD12_112") (pintype "bidirectional"))
    )
    (net (code "86") (name "unconnected-(U1A-PD13-Pad113)") (class "Default")
      (node (ref "U1") (pin "113") (pinfunction "PD13_113") (pintype "bidirectional"))
    )
    (net (code "87") (name "unconnected-(U1A-PD14-Pad116)") (class "Default")
      (node (ref "U1") (pin "116") (pinfunction "PD14_116") (pintype "bidirectional"))
    )
    (net (code "88") (name "unconnected-(U1A-PD15-Pad117)") (class "Default")
      (node (ref "U1") (pin "117") (pinfunction "PD15_117") (pintype "bidirectional"))
    )
    (net (code "89") (name "unconnected-(U1A-PE0-Pad200)") (class "Default")
      (node (ref "U1") (pin "200") (pinfunction "PE0_200") (pintype "bidirectional"))
    )
    (net (code "90") (name "unconnected-(U1A-PE1-Pad201)") (class "Default")
      (node (ref "U1") (pin "201") (pinfunction "PE1_201") (pintype "bidirectional"))
    )
    (net (code "91") (name "unconnected-(U1A-PE2-Pad1)") (class "Default")
      (node (ref "U1") (pin "1") (pinfunction "PE2_1") (pintype "bidirectional"))
    )
    (net (code "92") (name "unconnected-(U1A-PE3-Pad2)") (class "Default")
      (node (ref "U1") (pin "2") (pinfunction "PE3_2") (pintype "bidirectional"))
    )
    (net (code "93") (name "unconnected-(U1A-PE4-Pad3)") (class "Default")
      (node (ref "U1") (pin "3") (pinfunction "PE4_3") (pintype "bidirectional"))
    )
    (net (code "94") (name "unconnected-(U1A-PE5-Pad4)") (class "Default")
      (node (ref "U1") (pin "4") (pinfunction "PE5_4") (pintype "bidirectional"))
    )
    (net (code "95") (name "unconnected-(U1A-PE6-Pad5)") (class "Default")
      (node (ref "U1") (pin "5") (pinfunction "PE6_5") (pintype "bidirectional"))
    )
    (net (code "96") (name "unconnected-(U1A-PE7-Pad79)") (class "Default")
      (node (ref "U1") (pin "79") (pinfunction "PE7_79") (pintype "bidirectional"))
    )
    (net (code "97") (name "unconnected-(U1A-PE8-Pad80)") (class "Default")
      (node (ref "U1") (pin "80") (pinfunction "PE8_80") (pintype "bidirectional"))
    )
    (net (code "98") (name "unconnected-(U1A-PE9-Pad81)") (class "Default")
      (node (ref "U1") (pin "81") (pinfunction "PE9_81") (pintype "bidirectional"))
    )
    (net (code "99") (name "unconnected-(U1A-PE10-Pad84)") (class "Default")
      (node (ref "U1") (pin "84") (pinfunction "PE10_84") (pintype "bidirectional"))
    )
    (net (code "100") (name "unconnected-(U1A-PE11-Pad85)") (class "Default")
      (node (ref "U1") (pin "85") (pinfunction "PE11_85") (pintype "bidirectional"))
    )
    (net (code "101") (name "unconnected-(U1A-PE12-Pad86)") (class "Default")
      (node (ref "U1") (pin "86") (pinfunction "PE12_86") (pintype "bidirectional"))
    )
    (net (code "102") (name "unconnected-(U1A-PE13-Pad87)") (class "Default")
      (node (ref "U1") (pin "87") (pinfunction "PE13_87") (pintype "bidirectional"))
    )
    (net (code "103") (name "unconnected-(U1A-PE14-Pad88)") (class "Default")
      (node (ref "U1") (pin "88") (pinfunction "PE14_88") (pintype "bidirectional"))
    )
    (net (code "104") (name "unconnected-(U1A-PE15-Pad89)") (class "Default")
      (node (ref "U1") (pin "89") (pinfunction "PE15_89") (pintype "bidirectional"))
    )
    (net (code "105") (name "unconnected-(U1A-PF0-Pad16)") (class "Default")
      (node (ref "U1") (pin "16") (pinfunction "PF0_16") (pintype "bidirectional"))
    )
    (net (code "106") (name "unconnected-(U1A-PF1-Pad17)") (class "Default")
      (node (ref "U1") (pin "17") (pinfunction "PF1_17") (pintype "bidirectional"))
    )
    (net (code "107") (name "unconnected-(U1A-PF2-Pad18)") (class "Default")
      (node (ref "U1") (pin "18") (pinfunction "PF2_18") (pintype "bidirectional"))
    )
    (net (code "108") (name "unconnected-(U1A-PF3-Pad22)") (class "Default")
      (node (ref "U1") (pin "22") (pinfunction "PF3_22") (pintype "bidirectional"))
    )
    (net (code "109") (name "unconnected-(U1A-PF4-Pad23)") (class "Default")
      (node (ref "U1") (pin "23") (pinfunction "PF4_23") (pintype "bidirectional"))
    )
    (net (code "110") (name "unconnected-(U1A-PF5-Pad24)") (class "Default")
      (node (ref "U1") (pin "24") (pinfunction "PF5_24") (pintype "bidirectional"))
    )
    (net (code "111") (name "unconnected-(U1A-PF6-Pad27)") (class "Default")
      (node (ref "U1") (pin "27") (pinfunction "PF6_27") (pintype "bidirectional"))
    )
    (net (code "112") (name "unconnected-(U1A-PF7-Pad28)") (class "Default")
      (node (ref "U1") (pin "28") (pinfunction "PF7_28") (pintype "bidirectional"))
    )
    (net (code "113") (name "unconnected-(U1A-PF8-Pad29)") (class "Default")
      (node (ref "U1") (pin "29") (pinfunction "PF8_29") (pintype "bidirectional"))
    )
    (net (code "114") (name "unconnected-(U1A-PF9-Pad30)") (class "Default")
      (node (ref "U1") (pin "30") (pinfunction "PF9_30") (pintype "bidirectional"))
    )
    (net (code "115") (name "unconnected-(U1A-PF10-Pad31)") (class "Default")
      (node (ref "U1") (pin "31") (pinfunction "PF10_31") (pintype "bidirectional"))
    )
    (net (code "116") (name "unconnected-(U1A-PF11-Pad70)") (class "Default")
      (node (ref "U1") (pin "70") (pinfunction "PF11_70") (pintype "bidirectional"))
    )
    (net (code "117") (name "unconnected-(U1A-PF12-Pad71)") (class "Default")
      (node (ref "U1") (pin "71") (pinfunction "PF12_71") (pintype "bidirectional"))
    )
    (net (code "118") (name "unconnected-(U1A-PF13-Pad74)") (class "Default")
      (node (ref "U1") (pin "74") (pinfunction "PF13_74") (pintype "bidirectional"))
    )
    (net (code "119") (name "unconnected-(U1A-PF14-Pad75)") (class "Default")
      (node (ref "U1") (pin "75") (pinfunction "PF14_75") (pintype "bidirectional"))
    )
    (net (code "120") (name "unconnected-(U1A-PF15-Pad76)") (class "Default")
      (node (ref "U1") (pin "76") (pinfunction "PF15_76") (pintype "bidirectional"))
    )
    (net (code "121") (name "unconnected-(U1B-PG0-Pad77)") (class "Default")
      (node (ref "U1") (pin "77") (pinfunction "PG0_77") (pintype "bidirectional"))
    )
    (net (code "122") (name "unconnected-(U1B-PG1-Pad78)") (class "Default")
      (node (ref "U1") (pin "78") (pinfunction "PG1_78") (pintype "bidirectional"))
    )
    (net (code "123") (name "unconnected-(U1B-PG2-Pad129)") (class "Default")
      (node (ref "U1") (pin "129") (pinfunction "PG2_129") (pintype "bidirectional"))
    )
    (net (code "124") (name "unconnected-(U1B-PG3-Pad130)") (class "Default")
      (node (ref "U1") (pin "130") (pinfunction "PG3_130") (pintype "bidirectional"))
    )
    (net (code "125") (name "unconnected-(U1B-PG4-Pad131)") (class "Default")
      (node (ref "U1") (pin "131") (pinfunction "PG4_131") (pintype "bidirectional"))
    )
    (net (code "126") (name "unconnected-(U1B-PG5-Pad132)") (class "Default")
      (node (ref "U1") (pin "132") (pinfunction "PG5_132") (pintype "bidirectional"))
    )
    (net (code "127") (name "unconnected-(U1B-PG6-Pad133)") (class "Default")
      (node (ref "U1") (pin "133") (pinfunction "PG6_133") (pintype "bidirectional"))
    )
    (net (code "128") (name "unconnected-(U1B-PG7-Pad134)") (class "Default")
      (node (ref "U1") (pin "134") (pinfunction "PG7_134") (pintype "bidirectional"))
    )
    (net (code "129") (name "unconnected-(U1B-PG8-Pad135)") (class "Default")
      (node (ref "U1") (pin "135") (pinfunction "PG8_135") (pintype "bidirectional"))
    )
    (net (code "130") (name "unconnected-(U1B-PG9-Pad178)") (class "Default")
      (node (ref "U1") (pin "178") (pinfunction "PG9_178") (pintype "bidirectional"))
    )
    (net (code "131") (name "unconnected-(U1B-PG10-Pad179)") (class "Default")
      (node (ref "U1") (pin "179") (pinfunction "PG10_179") (pintype "bidirectional"))
    )
    (net (code "132") (name "unconnected-(U1B-PG11-Pad180)") (class "Default")
      (node (ref "U1") (pin "180") (pinfunction "PG11_180") (pintype "bidirectional"))
    )
    (net (code "133") (name "unconnected-(U1B-PG12-Pad181)") (class "Default")
      (node (ref "U1") (pin "181") (pinfunction "PG12_181") (pintype "bidirectional"))
    )
    (net (code "134") (name "unconnected-(U1B-PG13-Pad182)") (class "Default")
      (node (ref "U1") (pin "182") (pinfunction "PG13_182") (pintype "bidirectional"))
    )
    (net (code "135") (name "unconnected-(U1B-PG14-Pad183)") (class "Default")
      (node (ref "U1") (pin "183") (pinfunction "PG14_183") (pintype "bidirectional"))
    )
    (net (code "136") (name "unconnected-(U1B-PG15-Pad191)") (class "Default")
      (node (ref "U1") (pin "191") (pinfunction "PG15_191") (pintype "bidirectional"))
    )
    (net (code "137") (name "unconnected-(U1B-PH2-Pad46)") (class "Default")
      (node (ref "U1") (pin "46") (pinfunction "PH2_46") (pintype "bidirectional"))
    )
    (net (code "138") (name "unconnected-(U1B-PH3-Pad47)") (class "Default")
      (node (ref "U1") (pin "47") (pinfunction "PH3_47") (pintype "bidirectional"))
    )
    (net (code "139") (name "unconnected-(U1B-PH4-Pad48)") (class "Default")
      (node (ref "U1") (pin "48") (pinfunction "PH4_48") (pintype "bidirectional"))
    )
    (net (code "140") (name "unconnected-(U1B-PH5-Pad49)") (class "Default")
      (node (ref "U1") (pin "49") (pinfunction "PH5_49") (pintype "bidirectional"))
    )
    (net (code "141") (name "unconnected-(U1B-PH6-Pad96)") (class "Default")
      (node (ref "U1") (pin "96") (pinfunction "PH6_96") (pintype "bidirectional"))
    )
    (net (code "142") (name "unconnected-(U1B-PH7-Pad97)") (class "Default")
      (node (ref "U1") (pin "97") (pinfunction "PH7_97") (pintype "bidirectional"))
    )
    (net (code "143") (name "unconnected-(U1B-PH8-Pad98)") (class "Default")
      (node (ref "U1") (pin "98") (pinfunction "PH8_98") (pintype "bidirectional"))
    )
    (net (code "144") (name "unconnected-(U1B-PH9-Pad99)") (class "Default")
      (node (ref "U1") (pin "99") (pinfunction "PH9_99") (pintype "bidirectional"))
    )
    (net (code "145") (name "unconnected-(U1B-PH10-Pad100)") (class "Default")
      (node (ref "U1") (pin "100") (pinfunction "PH10_100") (pintype "bidirectional"))
    )
    (net (code "146") (name "unconnected-(U1B-PH11-Pad101)") (class "Default")
      (node (ref "U1") (pin "101") (pinfunction "PH11_101") (pintype "bidirectional"))
    )
    (net (code "147") (name "unconnected-(U1B-PH12-Pad102)") (class "Default")
      (node (ref "U1") (pin "102") (pinfunction "PH12_102") (pintype "bidirectional"))
    )
    (net (code "148") (name "unconnected-(U1B-PH13-Pad151)") (class "Default")
      (node (ref "U1") (pin "151") (pinfunction "PH13_151") (pintype "bidirectional"))
    )
    (net (code "149") (name "unconnected-(U1B-PH14-Pad152)") (class "Default")
      (node (ref "U1") (pin "152") (pinfunction "PH14_152") (pintype "bidirectional"))
    )
    (net (code "150") (name "unconnected-(U1B-PH15-Pad153)") (class "Default")
      (node (ref "U1") (pin "153") (pinfunction "PH15_153") (pintype "bidirectional"))
    )
    (net (code "151") (name "unconnected-(U1B-PI0-Pad154)") (class "Default")
      (node (ref "U1") (pin "154") (pinfunction "PI0_154") (pintype "bidirectional"))
    )
    (net (code "152") (name "unconnected-(U1B-PI1-Pad155)") (class "Default")
      (node (ref "U1") (pin "155") (pinfunction "PI1_155") (pintype "bidirectional"))
    )
    (net (code "153") (name "unconnected-(U1B-PI2-Pad156)") (class "Default")
      (node (ref "U1") (pin "156") (pinfunction "PI2_156") (pintype "bidirectional"))
    )
    (net (code "154") (name "unconnected-(U1B-PI3-Pad157)") (class "Default")
      (node (ref "U1") (pin "157") (pinfunction "PI3_157") (pintype "bidirectional"))
    )
    (net (code "155") (name "unconnected-(U1B-PI4-Pad205)") (class "Default")
      (node (ref "U1") (pin "205") (pinfunction "PI4_205") (pintype "bidirectional"))
    )
    (net (code "156") (name "unconnected-(U1B-PI5-Pad206)") (class "Default")
      (node (ref "U1") (pin "206") (pinfunction "PI5_206") (pintype "bidirectional"))
    )
    (net (code "157") (name "unconnected-(U1B-PI6-Pad207)") (class "Default")
      (node (ref "U1") (pin "207") (pinfunction "PI6_207") (pintype "bidirectional"))
    )
    (net (code "158") (name "unconnected-(U1B-PI7-Pad208)") (class "Default")
      (node (ref "U1") (pin "208") (pinfunction "PI7_208") (pintype "bidirectional"))
    )
    (net (code "159") (name "unconnected-(U1B-PI8-Pad7)") (class "Default")
      (node (ref "U1") (pin "7") (pinfunction "PI8_7") (pintype "bidirectional"))
    )
    (net (code "160") (name "unconnected-(U1B-PI9-Pad11)") (class "Default")
      (node (ref "U1") (pin "11") (pinfunction "PI9_11") (pintype "bidirectional"))
    )
    (net (code "161") (name "unconnected-(U1B-PI10-Pad12)") (class "Default")
      (node (ref "U1") (pin "12") (pinfunction "PI10_12") (pintype "bidirectional"))
    )
    (net (code "162") (name "unconnected-(U1B-PI11-Pad13)") (class "Default")
      (node (ref "U1") (pin "13") (pinfunction "PI11_13") (pintype "bidirectional"))
    )
    (net (code "163") (name "unconnected-(U1B-PI12-Pad19)") (class "Default")
      (node (ref "U1") (pin "19") (pinfunction "PI12_19") (pintype "bidirectional"))
    )
    (net (code "164") (name "unconnected-(U1B-PI13-Pad20)") (class "Default")
      (node (ref "U1") (pin "20") (pinfunction "PI13_20") (pintype "bidirectional"))
    )
    (net (code "165") (name "unconnected-(U1B-PI14-Pad21)") (class "Default")
      (node (ref "U1") (pin "21") (pinfunction "PI14_21") (pintype "bidirectional"))
    )
    (net (code "166") (name "unconnected-(U1B-PI15-Pad64)") (class "Default")
      (node (ref "U1") (pin "64") (pinfunction "PI15_64") (pintype "bidirectional"))
    )
    (net (code "167") (name "unconnected-(U1B-PJ0-Pad65)") (class "Default")
      (node (ref "U1") (pin "65") (pinfunction "PJ0_65") (pintype "bidirectional"))
    )
    (net (code "168") (name "unconnected-(U1B-PJ1-Pad66)") (class "Default")
      (node (ref "U1") (pin "66") (pinfunction "PJ1_66") (pintype "bidirectional"))
    )
    (net (code "169") (name "unconnected-(U1B-PJ2-Pad67)") (class "Default")
      (node (ref "U1") (pin "67") (pinfunction "PJ2_67") (pintype "bidirectional"))
    )
    (net (code "170") (name "unconnected-(U1B-PJ3-Pad68)") (class "Default")
      (node (ref "U1") (pin "68") (pinfunction "PJ3_68") (pintype "bidirectional"))
    )
    (net (code "171") (name "unconnected-(U1B-PJ4-Pad69)") (class "Default")
      (node (ref "U1") (pin "69") (pinfunction "PJ4_69") (pintype "bidirectional"))
    )
    (net (code "172") (name "unconnected-(U1B-PJ5-Pad95)") (class "Default")
      (node (ref "U1") (pin "95") (pinfunction "PJ5_95") (pintype "bidirectional"))
    )
    (net (code "173") (name "unconnected-(U1B-PJ12-Pad174)") (class "Default")
      (node (ref "U1") (pin "174") (pinfunction "PJ12_174") (pintype "bidirectional"))
    )
    (net (code "174") (name "unconnected-(U1B-PJ13-Pad175)") (class "Default")
      (node (ref "U1") (pin "175") (pinfunction "PJ13_175") (pintype "bidirectional"))
    )
    (net (code "175") (name "unconnected-(U1B-PJ14-Pad176)") (class "Default")
      (node (ref "U1") (pin "176") (pinfunction "PJ14_176") (pintype "bidirectional"))
    )
    (net (code "176") (name "unconnected-(U1B-PK3-Pad186)") (class "Default")
      (node (ref "U1") (pin "186") (pinfunction "PK3_186") (pintype "bidirectional"))
    )
    (net (code "177") (name "unconnected-(U1B-PK4-Pad187)") (class "Default")
      (node (ref "U1") (pin "187") (pinfunction "PK4_187") (pintype "bidirectional"))
    )
    (net (code "178") (name "unconnected-(U1B-PK5-Pad188)") (class "Default")
      (node (ref "U1") (pin "188") (pinfunction "PK5_188") (pintype "bidirectional"))
    )
    (net (code "179") (name "unconnected-(U1B-PK6-Pad189)") (class "Default")
      (node (ref "U1") (pin "189") (pinfunction "PK6_189") (pintype "bidirectional"))
    )
  )
)
